# Solenoid_Current_Detector.net
KiCad netlist of a schematic drawn in Altium Designer
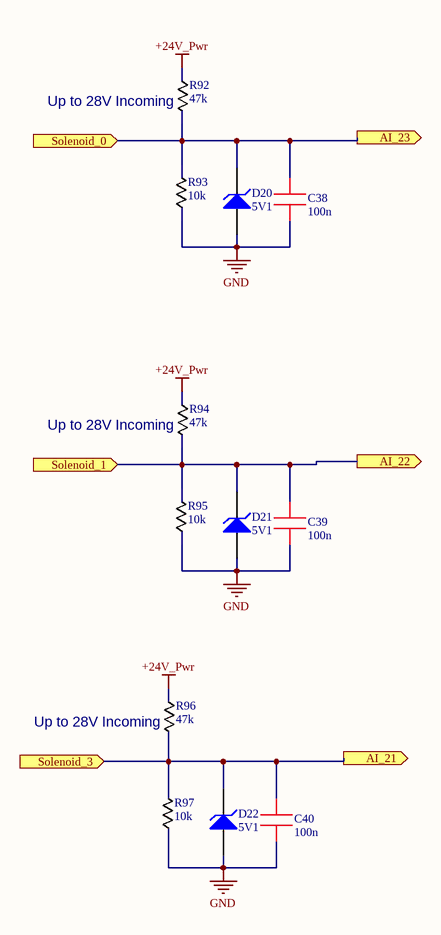
[diagram p0: Solenoid Current Detector.SchDoc]

(export (version "E")
  (design (tool "Eeschema 10.0.6"))
  (components
    (comp (ref "C38")
      (value "100n")
      (footprint "0603")
      (description "CC0603KRX7R9BB104")
      (libsource (lib "kontr") (part "0603 CAP"))
    )
    (comp (ref "C39")
      (value "100n")
      (footprint "0603")
      (description "CC0603KRX7R9BB104")
      (libsource (lib "kontr") (part "0603 CAP"))
    )
    (comp (ref "C40")
      (value "100n")
      (footprint "0603")
      (description "CC0603KRX7R9BB104")
      (libsource (lib "kontr") (part "0603 CAP"))
    )
    (comp (ref "D20")
      (value "5V1")
      (footprint "PcbLib1:SOT23")
      (description "BZX84C5V1LT1G")
      (libsource (lib "Miscellaneous Devices") (part "D Zener"))
    )
    (comp (ref "D21")
      (value "5V1")
      (footprint "PcbLib1:SOT23")
      (description "BZX84C5V1LT1G")
      (libsource (lib "Miscellaneous Devices") (part "D Zener"))
    )
    (comp (ref "D22")
      (value "5V1")
      (footprint "PcbLib1:SOT23")
      (description "BZX84C5V1LT1G")
      (libsource (lib "Miscellaneous Devices") (part "D Zener"))
    )
    (comp (ref "R92")
      (value "47k")
      (footprint "0603")
      (description "RC0603JR-0747K")
      (libsource (lib "kontr") (part "0603 RES"))
    )
    (comp (ref "R93")
      (value "10k")
      (footprint "0603")
      (description "RT0603FRE0710KL")
      (libsource (lib "kontr") (part "0603 RES"))
    )
    (comp (ref "R94")
      (value "47k")
      (footprint "0603")
      (description "RC0603JR-0747K")
      (libsource (lib "kontr") (part "0603 RES"))
    )
    (comp (ref "R95")
      (value "10k")
      (footprint "0603")
      (description "RT0603FRE0710KL")
      (libsource (lib "kontr") (part "0603 RES"))
    )
    (comp (ref "R96")
      (value "47k")
      (footprint "0603")
      (description "RC0603JR-0747K")
      (libsource (lib "kontr") (part "0603 RES"))
    )
    (comp (ref "R97")
      (value "10k")
      (footprint "0603")
      (description "RT0603FRE0710KL")
      (libsource (lib "kontr") (part "0603 RES"))
    )
  )
  (nets
    (net (code "1") (name "+24V_Pwr") (class "Default")
      (node (ref "R92") (pin "1") (pintype "passive"))
      (node (ref "R94") (pin "1") (pintype "passive"))
      (node (ref "R96") (pin "1") (pintype "passive"))
    )
    (net (code "2") (name "/AI_21") (class "Default")
      (node (ref "C40") (pin "2") (pinfunction "2_2") (pintype "passive"))
      (node (ref "D22") (pin "2") (pinfunction "K_2") (pintype "passive"))
      (node (ref "R96") (pin "2") (pintype "passive"))
      (node (ref "R97") (pin "2") (pintype "passive"))
    )
    (net (code "3") (name "/AI_22") (class "Default")
      (node (ref "C39") (pin "2") (pinfunction "2_2") (pintype "passive"))
      (node (ref "D21") (pin "2") (pinfunction "K_2") (pintype "passive"))
      (node (ref "R94") (pin "2") (pintype "passive"))
      (node (ref "R95") (pin "2") (pintype "passive"))
    )
    (net (code "4") (name "/AI_23") (class "Default")
      (node (ref "C38") (pin "2") (pinfunction "2_2") (pintype "passive"))
      (node (ref "D20") (pin "2") (pinfunction "K_2") (pintype "passive"))
      (node (ref "R92") (pin "2") (pintype "passive"))
      (node (ref "R93") (pin "2") (pintype "passive"))
    )
    (net (code "5") (name "GND") (class "Default")
      (node (ref "C38") (pin "1") (pinfunction "1_1") (pintype "passive"))
      (node (ref "C39") (pin "1") (pinfunction "1_1") (pintype "passive"))
      (node (ref "C40") (pin "1") (pinfunction "1_1") (pintype "passive"))
      (node (ref "D20") (pin "1") (pinfunction "A_1") (pintype "passive"))
      (node (ref "D21") (pin "1") (pinfunction "A_1") (pintype "passive"))
      (node (ref "D22") (pin "1") (pinfunction "A_1") (pintype "passive"))
      (node (ref "R93") (pin "1") (pintype "passive"))
      (node (ref "R95") (pin "1") (pintype "passive"))
      (node (ref "R97") (pin "1") (pintype "passive"))
    )
  )
)
